# team18.net
KiCad netlist of a schematic drawn in EAGLE
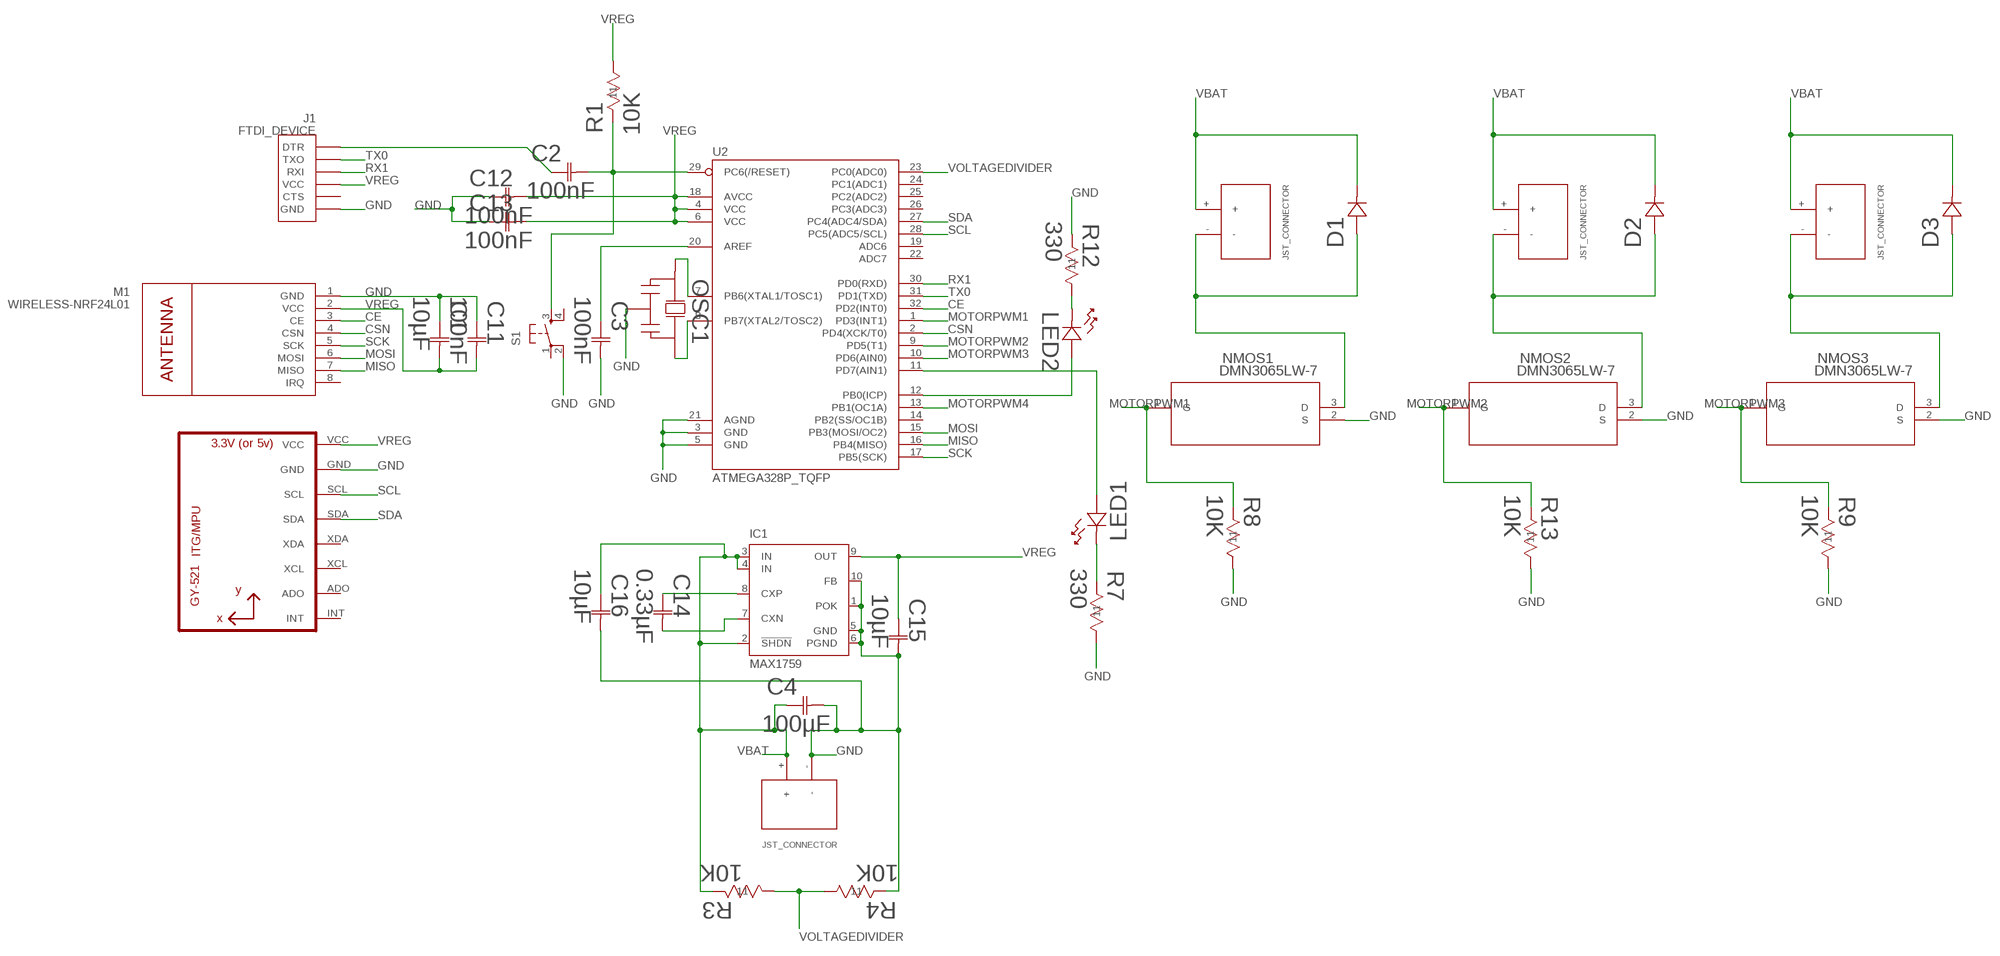
[diagram p0: schematic, sheet 1, part 1 of 2]
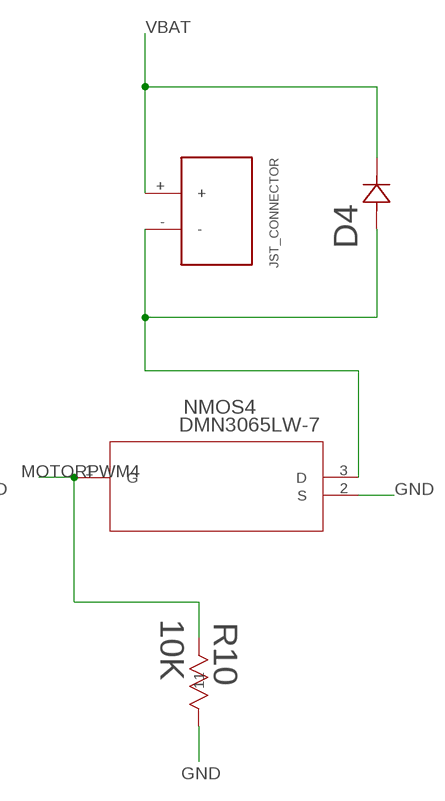
[diagram p1: schematic, sheet 1, part 2 of 2]

(export (version "E")
  (design (tool "Eeschema 10.0.6"))
  (components
    (comp (ref "BATTERY")
      (value "JST_CONNECTOR_FEMALE")
      (footprint "eagle-import:JST_CONNECTOR_FEMALE")
      (libsource (lib "eagle-import") (part "JST_CONNECTOR_FEMALE"))
    )
    (comp (ref "C1")
      (value "10µF")
      (footprint "eagle-import:G-188")
      (fields (field (name "MANUFACTURER_PART_NUMBER") "GRM188R60J106ME47D"))
      (libsource (lib "eagle-import") (part "GRM188R60J106ME47D"))
    )
    (comp (ref "C2")
      (value "100nF")
      (footprint "eagle-import:CAP_1608")
      (fields (field (name "MANUFACTURER_PART_NUMBER") "C1608X5R1H104K080AA"))
      (libsource (lib "eagle-import") (part "C1608X5R1H104K080AA"))
    )
    (comp (ref "C3")
      (value "100nF")
      (footprint "eagle-import:CAP_1608")
      (fields (field (name "MANUFACTURER_PART_NUMBER") "C1608X5R1H104K080AA"))
      (libsource (lib "eagle-import") (part "C1608X5R1H104K080AA"))
    )
    (comp (ref "C4")
      (value "100µF")
      (footprint "eagle-import:CAP_3216")
      (fields (field (name "MANUFACTURER_PART_NUMBER") "C3216X5R0J107M160AB"))
      (libsource (lib "eagle-import") (part "C3216X5R0J107M160AB"))
    )
    (comp (ref "C11")
      (value "100nF")
      (footprint "eagle-import:CAP_1608")
      (fields (field (name "MANUFACTURER_PART_NUMBER") "C1608X5R1H104K080AA"))
      (libsource (lib "eagle-import") (part "C1608X5R1H104K080AA"))
    )
    (comp (ref "C12")
      (value "100nF")
      (footprint "eagle-import:CAP_1608")
      (fields (field (name "MANUFACTURER_PART_NUMBER") "C1608X5R1H104K080AA"))
      (libsource (lib "eagle-import") (part "C1608X5R1H104K080AA"))
    )
    (comp (ref "C13")
      (value "100nF")
      (footprint "eagle-import:CAP_1608")
      (fields (field (name "MANUFACTURER_PART_NUMBER") "C1608X5R1H104K080AA"))
      (libsource (lib "eagle-import") (part "C1608X5R1H104K080AA"))
    )
    (comp (ref "C14")
      (value "0.33µF")
      (footprint "eagle-import:G-188")
      (fields (field (name "MANUFACTURER_PART_NUMBER") "GRM188R71C334KA01D"))
      (libsource (lib "eagle-import") (part "GRM188R71C334KA01D"))
    )
    (comp (ref "C15")
      (value "10µF")
      (footprint "eagle-import:G-188")
      (fields (field (name "MANUFACTURER_PART_NUMBER") "GRM188R60J106ME47D"))
      (libsource (lib "eagle-import") (part "GRM188R60J106ME47D"))
    )
    (comp (ref "C16")
      (value "10µF")
      (footprint "eagle-import:G-188")
      (fields (field (name "MANUFACTURER_PART_NUMBER") "GRM188R60J106ME47D"))
      (libsource (lib "eagle-import") (part "GRM188R60J106ME47D"))
    )
    (comp (ref "D1")
      (value "BAT60JFILM")
      (footprint "eagle-import:SOD-323")
      (libsource (lib "eagle-import") (part "BAT60JFILM"))
    )
    (comp (ref "D2")
      (value "BAT60JFILM")
      (footprint "eagle-import:SOD-323")
      (libsource (lib "eagle-import") (part "BAT60JFILM"))
    )
    (comp (ref "D3")
      (value "BAT60JFILM")
      (footprint "eagle-import:SOD-323")
      (libsource (lib "eagle-import") (part "BAT60JFILM"))
    )
    (comp (ref "D4")
      (value "BAT60JFILM")
      (footprint "eagle-import:SOD-323")
      (libsource (lib "eagle-import") (part "BAT60JFILM"))
    )
    (comp (ref "IC1")
      (value "MAX1759")
      (footprint "eagle-import:UMAX10")
      (fields (field (name "MF") "MAXIM") (field (name "MPN") "MAX1759EUB+"))
      (libsource (lib "eagle-import") (part "MAX1759"))
    )
    (comp (ref "J1")
      (value "FTDI_DEVICE")
      (footprint "eagle-import:FTDI_DEVICE_SIDE")
      (libsource (lib "eagle-import") (part "FTDI_DEVICE"))
    )
    (comp (ref "LED1")
      (value "5988070107F")
      (footprint "eagle-import:LED_DIALIGHT_598")
      (libsource (lib "eagle-import") (part "LED Red_5988070107F"))
    )
    (comp (ref "LED2")
      (value "5988070107F")
      (footprint "eagle-import:LED_DIALIGHT_598")
      (libsource (lib "eagle-import") (part "5988070107F"))
    )
    (comp (ref "M1")
      (value "WIRELESS-NRF24L01")
      (footprint "eagle-import:WIRELESS-NRF24L01")
      (libsource (lib "eagle-import") (part "WIRELESS-NRF24L01"))
    )
    (comp (ref "MOTOR1")
      (value "JST_CONNECTOR_FEMALE")
      (footprint "eagle-import:JST_CONNECTOR_FEMALE")
      (libsource (lib "eagle-import") (part "JST_CONNECTOR_FEMALE"))
    )
    (comp (ref "MOTOR2")
      (value "JST_CONNECTOR_FEMALE")
      (footprint "eagle-import:JST_CONNECTOR_FEMALE")
      (libsource (lib "eagle-import") (part "JST_CONNECTOR_FEMALE"))
    )
    (comp (ref "MOTOR3")
      (value "JST_CONNECTOR_FEMALE")
      (footprint "eagle-import:JST_CONNECTOR_FEMALE")
      (libsource (lib "eagle-import") (part "JST_CONNECTOR_FEMALE"))
    )
    (comp (ref "MOTOR4")
      (value "JST_CONNECTOR_FEMALE")
      (footprint "eagle-import:JST_CONNECTOR_FEMALE")
      (libsource (lib "eagle-import") (part "JST_CONNECTOR_FEMALE"))
    )
    (comp (ref "NMOS1")
      (value "DMN3065LW-7")
      (footprint "eagle-import:SOT-323W_NEW")
      (libsource (lib "eagle-import") (part "DMN3065LW-7"))
    )
    (comp (ref "NMOS2")
      (value "DMN3065LW-7")
      (footprint "eagle-import:SOT-323W_NEW")
      (libsource (lib "eagle-import") (part "DMN3065LW-7"))
    )
    (comp (ref "NMOS3")
      (value "DMN3065LW-7")
      (footprint "eagle-import:SOT-323W_NEW")
      (libsource (lib "eagle-import") (part "DMN3065LW-7"))
    )
    (comp (ref "NMOS4")
      (value "DMN3065LW-7")
      (footprint "eagle-import:SOT-323W_NEW")
      (libsource (lib "eagle-import") (part "DMN3065LW-7"))
    )
    (comp (ref "OSC1")
      (value "CSTCE8M00G52-R0")
      (footprint "eagle-import:CSTCE")
      (fields (field (name "MANUFACTURER_PART_NUMBER") "CSTCE8M00G52R0"))
      (libsource (lib "eagle-import") (part "CSTCE8M00G52-R0"))
    )
    (comp (ref "R1")
      (value "10K")
      (footprint "eagle-import:0603")
      (fields (field (name "MANUFACTURER_PART_NUMBER") "MCT06030C1002FP500"))
      (libsource (lib "eagle-import") (part "MCT06030C1002FP500"))
    )
    (comp (ref "R3")
      (value "10K")
      (footprint "eagle-import:0603")
      (fields (field (name "MANUFACTURER_PART_NUMBER") "MCT06030C1002FP500"))
      (libsource (lib "eagle-import") (part "MCT06030C1002FP500"))
    )
    (comp (ref "R4")
      (value "10K")
      (footprint "eagle-import:0603")
      (fields (field (name "MANUFACTURER_PART_NUMBER") "MCT06030C1002FP500"))
      (libsource (lib "eagle-import") (part "MCT06030C1002FP500"))
    )
    (comp (ref "R7")
      (value "330")
      (footprint "eagle-import:BO_CR0603")
      (fields (field (name "MANUFACTURER_PART_NUMBER") "CR0603JW331ELF"))
      (libsource (lib "eagle-import") (part "CR0603-JW-331ELF"))
    )
    (comp (ref "R8")
      (value "10K")
      (footprint "eagle-import:0603")
      (fields (field (name "MANUFACTURER_PART_NUMBER") "MCT06030C1002FP500"))
      (libsource (lib "eagle-import") (part "MCT06030C1002FP500"))
    )
    (comp (ref "R9")
      (value "10K")
      (footprint "eagle-import:0603")
      (fields (field (name "MANUFACTURER_PART_NUMBER") "MCT06030C1002FP500"))
      (libsource (lib "eagle-import") (part "MCT06030C1002FP500"))
    )
    (comp (ref "R10")
      (value "10K")
      (footprint "eagle-import:0603")
      (fields (field (name "MANUFACTURER_PART_NUMBER") "MCT06030C1002FP500"))
      (libsource (lib "eagle-import") (part "MCT06030C1002FP500"))
    )
    (comp (ref "R12")
      (value "330")
      (footprint "eagle-import:BO_CR0603")
      (fields (field (name "MANUFACTURER_PART_NUMBER") "CR0603JW331ELF"))
      (libsource (lib "eagle-import") (part "CR0603-JW-331ELF"))
    )
    (comp (ref "R13")
      (value "10K")
      (footprint "eagle-import:0603")
      (fields (field (name "MANUFACTURER_PART_NUMBER") "MCT06030C1002FP500"))
      (libsource (lib "eagle-import") (part "MCT06030C1002FP500"))
    )
    (comp (ref "S1")
      (value "TAC_SWITCHSMD")
      (footprint "eagle-import:TACTILE_SWITCH_SMD")
      (libsource (lib "eagle-import") (part "TAC_SWITCHSMD"))
    )
    (comp (ref "U1")
      (value "GY-521MPU6050")
      (footprint "eagle-import:GY-521")
      (libsource (lib "eagle-import") (part "GY-521MPU6050"))
    )
    (comp (ref "U2")
      (value "ATMEGA328P_TQFP")
      (footprint "eagle-import:TQFP32-08")
      (libsource (lib "eagle-import") (part "ATMEGA328P_TQFP"))
    )
  )
  (nets
    (net (code "1") (name "/CE") (class "Default")
      (node (ref "M1") (pin "3") (pinfunction "CE_3") (pintype "bidirectional"))
      (node (ref "U2") (pin "32") (pinfunction "PD2(INT0)_32") (pintype "bidirectional"))
    )
    (net (code "2") (name "/CSN") (class "Default")
      (node (ref "M1") (pin "4") (pinfunction "CSN_4") (pintype "bidirectional"))
      (node (ref "U2") (pin "2") (pinfunction "PD4(XCK/T0)_2") (pintype "bidirectional"))
    )
    (net (code "3") (name "/GND") (class "Default")
      (node (ref "BATTERY") (pin "-") (pinfunction "-_-") (pintype "bidirectional"))
      (node (ref "C1") (pin "1") (pinfunction "11_1") (pintype "passive"))
      (node (ref "C11") (pin "1") (pinfunction "11_1") (pintype "passive"))
      (node (ref "C12") (pin "1") (pinfunction "11_1") (pintype "passive"))
      (node (ref "C13") (pin "1") (pinfunction "11_1") (pintype "passive"))
      (node (ref "C15") (pin "2") (pinfunction "22_2") (pintype "passive"))
      (node (ref "C16") (pin "2") (pinfunction "22_2") (pintype "passive"))
      (node (ref "C3") (pin "2") (pinfunction "22_2") (pintype "passive"))
      (node (ref "C4") (pin "2") (pinfunction "22_2") (pintype "passive"))
      (node (ref "IC1") (pin "1") (pinfunction "POK_1") (pintype "open_collector"))
      (node (ref "IC1") (pin "10") (pinfunction "FB_10") (pintype "input"))
      (node (ref "IC1") (pin "5") (pinfunction "GND_5") (pintype "power_in"))
      (node (ref "IC1") (pin "6") (pinfunction "PGND_6") (pintype "power_in"))
      (node (ref "J1") (pin "P$6") (pinfunction "GND_P$6") (pintype "bidirectional"))
      (node (ref "M1") (pin "1") (pinfunction "GND_1") (pintype "power_in"))
      (node (ref "NMOS1") (pin "2") (pinfunction "S_2") (pintype "passive"))
      (node (ref "NMOS2") (pin "2") (pinfunction "S_2") (pintype "passive"))
      (node (ref "NMOS3") (pin "2") (pinfunction "S_2") (pintype "passive"))
      (node (ref "NMOS4") (pin "2") (pinfunction "S_2") (pintype "passive"))
      (node (ref "OSC1") (pin "2") (pinfunction "22_2") (pintype "passive"))
      (node (ref "R10") (pin "2") (pinfunction "22_2") (pintype "passive"))
      (node (ref "R12") (pin "1") (pinfunction "11_1") (pintype "passive"))
      (node (ref "R13") (pin "2") (pinfunction "22_2") (pintype "passive"))
      (node (ref "R4") (pin "1") (pinfunction "11_1") (pintype "passive"))
      (node (ref "R7") (pin "2") (pinfunction "22_2") (pintype "passive"))
      (node (ref "R8") (pin "2") (pinfunction "22_2") (pintype "passive"))
      (node (ref "R9") (pin "2") (pinfunction "22_2") (pintype "passive"))
      (node (ref "S1") (pin "2") (pinfunction "2_2") (pintype "passive"))
      (node (ref "U1") (pin "GND") (pinfunction "GND_GND") (pintype "bidirectional"))
      (node (ref "U2") (pin "21") (pinfunction "AGND_21") (pintype "bidirectional"))
      (node (ref "U2") (pin "3") (pinfunction "GND_3") (pintype "bidirectional"))
      (node (ref "U2") (pin "5") (pinfunction "GND_5") (pintype "bidirectional"))
    )
    (net (code "4") (name "/MISO") (class "Default")
      (node (ref "M1") (pin "7") (pinfunction "MISO_7") (pintype "bidirectional"))
      (node (ref "U2") (pin "16") (pinfunction "PB4(MISO)_16") (pintype "bidirectional"))
    )
    (net (code "5") (name "/MOSI") (class "Default")
      (node (ref "M1") (pin "6") (pinfunction "MOSI_6") (pintype "bidirectional"))
      (node (ref "U2") (pin "15") (pinfunction "PB3(MOSI/OC2)_15") (pintype "bidirectional"))
    )
    (net (code "6") (name "/MOTORPWM1") (class "Default")
      (node (ref "NMOS1") (pin "1") (pinfunction "G_1") (pintype "passive"))
      (node (ref "R8") (pin "1") (pinfunction "11_1") (pintype "passive"))
      (node (ref "U2") (pin "1") (pinfunction "PD3(INT1)_1") (pintype "bidirectional"))
    )
    (net (code "7") (name "/MOTORPWM2") (class "Default")
      (node (ref "NMOS2") (pin "1") (pinfunction "G_1") (pintype "passive"))
      (node (ref "R13") (pin "1") (pinfunction "11_1") (pintype "passive"))
      (node (ref "U2") (pin "9") (pinfunction "PD5(T1)_9") (pintype "bidirectional"))
    )
    (net (code "8") (name "/MOTORPWM3") (class "Default")
      (node (ref "NMOS3") (pin "1") (pinfunction "G_1") (pintype "passive"))
      (node (ref "R9") (pin "1") (pinfunction "11_1") (pintype "passive"))
      (node (ref "U2") (pin "10") (pinfunction "PD6(AIN0)_10") (pintype "bidirectional"))
    )
    (net (code "9") (name "/MOTORPWM4") (class "Default")
      (node (ref "NMOS4") (pin "1") (pinfunction "G_1") (pintype "passive"))
      (node (ref "R10") (pin "1") (pinfunction "11_1") (pintype "passive"))
      (node (ref "U2") (pin "13") (pinfunction "PB1(OC1A)_13") (pintype "bidirectional"))
    )
    (net (code "10") (name "/RX1") (class "Default")
      (node (ref "J1") (pin "P$3") (pinfunction "RXI_P$3") (pintype "bidirectional"))
      (node (ref "U2") (pin "30") (pinfunction "PD0(RXD)_30") (pintype "bidirectional"))
    )
    (net (code "11") (name "/SCK") (class "Default")
      (node (ref "M1") (pin "5") (pinfunction "SCK_5") (pintype "bidirectional"))
      (node (ref "U2") (pin "17") (pinfunction "PB5(SCK)_17") (pintype "bidirectional"))
    )
    (net (code "12") (name "/SCL") (class "Default")
      (node (ref "U1") (pin "SCL") (pinfunction "SCL_SCL") (pintype "bidirectional"))
      (node (ref "U2") (pin "28") (pinfunction "PC5(ADC5/SCL)_28") (pintype "bidirectional"))
    )
    (net (code "13") (name "/SDA") (class "Default")
      (node (ref "U1") (pin "SDA") (pinfunction "SDA_SDA") (pintype "bidirectional"))
      (node (ref "U2") (pin "27") (pinfunction "PC4(ADC4/SDA)_27") (pintype "bidirectional"))
    )
    (net (code "14") (name "/TX0") (class "Default")
      (node (ref "J1") (pin "P$2") (pinfunction "TXO_P$2") (pintype "bidirectional"))
      (node (ref "U2") (pin "31") (pinfunction "PD1(TXD)_31") (pintype "bidirectional"))
    )
    (net (code "15") (name "/VBAT") (class "Default")
      (node (ref "BATTERY") (pin "+") (pinfunction "+_+") (pintype "bidirectional"))
      (node (ref "C16") (pin "1") (pinfunction "11_1") (pintype "passive"))
      (node (ref "C4") (pin "1") (pinfunction "11_1") (pintype "passive"))
      (node (ref "D1") (pin "1") (pinfunction "11_1") (pintype "passive"))
      (node (ref "D2") (pin "1") (pinfunction "11_1") (pintype "passive"))
      (node (ref "D3") (pin "1") (pinfunction "11_1") (pintype "passive"))
      (node (ref "D4") (pin "1") (pinfunction "11_1") (pintype "passive"))
      (node (ref "IC1") (pin "2") (pinfunction "~{SHDN}_2") (pintype "input"))
      (node (ref "IC1") (pin "3") (pinfunction "IN_3") (pintype "input"))
      (node (ref "IC1") (pin "4") (pinfunction "IN_4") (pintype "input"))
      (node (ref "MOTOR1") (pin "+") (pinfunction "+_+") (pintype "bidirectional"))
      (node (ref "MOTOR2") (pin "+") (pinfunction "+_+") (pintype "bidirectional"))
      (node (ref "MOTOR3") (pin "+") (pinfunction "+_+") (pintype "bidirectional"))
      (node (ref "MOTOR4") (pin "+") (pinfunction "+_+") (pintype "bidirectional"))
      (node (ref "R3") (pin "1") (pinfunction "11_1") (pintype "passive"))
    )
    (net (code "16") (name "/VOLTAGEDIVIDER") (class "Default")
      (node (ref "R3") (pin "2") (pinfunction "22_2") (pintype "passive"))
      (node (ref "R4") (pin "2") (pinfunction "22_2") (pintype "passive"))
      (node (ref "U2") (pin "23") (pinfunction "PC0(ADC0)_23") (pintype "bidirectional"))
    )
    (net (code "17") (name "/VREG") (class "Default")
      (node (ref "C1") (pin "2") (pinfunction "22_2") (pintype "passive"))
      (node (ref "C11") (pin "2") (pinfunction "22_2") (pintype "passive"))
      (node (ref "C12") (pin "2") (pinfunction "22_2") (pintype "passive"))
      (node (ref "C13") (pin "2") (pinfunction "22_2") (pintype "passive"))
      (node (ref "C15") (pin "1") (pinfunction "11_1") (pintype "passive"))
      (node (ref "IC1") (pin "9") (pinfunction "OUT_9") (pintype "passive"))
      (node (ref "J1") (pin "P$4") (pinfunction "VCC_P$4") (pintype "bidirectional"))
      (node (ref "M1") (pin "2") (pinfunction "VCC_2") (pintype "power_in"))
      (node (ref "R1") (pin "2") (pinfunction "22_2") (pintype "passive"))
      (node (ref "U1") (pin "VCC") (pinfunction "VCC_VCC") (pintype "bidirectional"))
      (node (ref "U2") (pin "18") (pinfunction "AVCC_18") (pintype "bidirectional"))
      (node (ref "U2") (pin "4") (pinfunction "VCC_4") (pintype "bidirectional"))
      (node (ref "U2") (pin "6") (pinfunction "VCC_6") (pintype "bidirectional"))
    )
    (net (code "18") (name "Net-(C2-11)") (class "Default")
      (node (ref "C2") (pin "1") (pinfunction "11_1") (pintype "passive"))
      (node (ref "J1") (pin "P$1") (pinfunction "DTR_P$1") (pintype "bidirectional"))
    )
    (net (code "19") (name "Net-(C2-22)") (class "Default")
      (node (ref "C2") (pin "2") (pinfunction "22_2") (pintype "passive"))
      (node (ref "R1") (pin "1") (pinfunction "11_1") (pintype "passive"))
      (node (ref "S1") (pin "3") (pinfunction "3_3") (pintype "passive"))
      (node (ref "U2") (pin "29") (pinfunction "PC6(/RESET)_29") (pintype "bidirectional"))
    )
    (net (code "20") (name "Net-(C3-11)") (class "Default")
      (node (ref "C3") (pin "1") (pinfunction "11_1") (pintype "passive"))
      (node (ref "U2") (pin "20") (pinfunction "AREF_20") (pintype "bidirectional"))
    )
    (net (code "21") (name "Net-(C14-11)") (class "Default")
      (node (ref "C14") (pin "1") (pinfunction "11_1") (pintype "passive"))
      (node (ref "IC1") (pin "8") (pinfunction "CXP_8") (pintype "input"))
    )
    (net (code "22") (name "Net-(C14-22)") (class "Default")
      (node (ref "C14") (pin "2") (pinfunction "22_2") (pintype "passive"))
      (node (ref "IC1") (pin "7") (pinfunction "CXN_7") (pintype "input"))
    )
    (net (code "23") (name "Net-(D1-22)") (class "Default")
      (node (ref "D1") (pin "2") (pinfunction "22_2") (pintype "passive"))
      (node (ref "MOTOR1") (pin "-") (pinfunction "-_-") (pintype "bidirectional"))
      (node (ref "NMOS1") (pin "3") (pinfunction "D_3") (pintype "passive"))
    )
    (net (code "24") (name "Net-(D2-22)") (class "Default")
      (node (ref "D2") (pin "2") (pinfunction "22_2") (pintype "passive"))
      (node (ref "MOTOR2") (pin "-") (pinfunction "-_-") (pintype "bidirectional"))
      (node (ref "NMOS2") (pin "3") (pinfunction "D_3") (pintype "passive"))
    )
    (net (code "25") (name "Net-(D3-22)") (class "Default")
      (node (ref "D3") (pin "2") (pinfunction "22_2") (pintype "passive"))
      (node (ref "MOTOR3") (pin "-") (pinfunction "-_-") (pintype "bidirectional"))
      (node (ref "NMOS3") (pin "3") (pinfunction "D_3") (pintype "passive"))
    )
    (net (code "26") (name "Net-(D4-22)") (class "Default")
      (node (ref "D4") (pin "2") (pinfunction "22_2") (pintype "passive"))
      (node (ref "MOTOR4") (pin "-") (pinfunction "-_-") (pintype "bidirectional"))
      (node (ref "NMOS4") (pin "3") (pinfunction "D_3") (pintype "passive"))
    )
    (net (code "27") (name "Net-(LED1-11)") (class "Default")
      (node (ref "LED1") (pin "1") (pinfunction "11_1") (pintype "passive"))
      (node (ref "R7") (pin "1") (pinfunction "11_1") (pintype "passive"))
    )
    (net (code "28") (name "Net-(LED1-22)") (class "Default")
      (node (ref "LED1") (pin "2") (pinfunction "22_2") (pintype "passive"))
      (node (ref "U2") (pin "11") (pinfunction "PD7(AIN1)_11") (pintype "bidirectional"))
    )
    (net (code "29") (name "Net-(LED2-11)") (class "Default")
      (node (ref "LED2") (pin "1") (pinfunction "11_1") (pintype "passive"))
      (node (ref "R12") (pin "2") (pinfunction "22_2") (pintype "passive"))
    )
    (net (code "30") (name "Net-(LED2-22)") (class "Default")
      (node (ref "LED2") (pin "2") (pinfunction "22_2") (pintype "passive"))
      (node (ref "U2") (pin "12") (pinfunction "PB0(ICP)_12") (pintype "bidirectional"))
    )
    (net (code "31") (name "Net-(OSC1-11)") (class "Default")
      (node (ref "OSC1") (pin "1") (pinfunction "11_1") (pintype "passive"))
      (node (ref "U2") (pin "8") (pinfunction "PB7(XTAL2/TOSC2)_8") (pintype "bidirectional"))
    )
    (net (code "32") (name "Net-(OSC1-33)") (class "Default")
      (node (ref "OSC1") (pin "3") (pinfunction "33_3") (pintype "passive"))
      (node (ref "U2") (pin "7") (pinfunction "PB6(XTAL1/TOSC1)_7") (pintype "bidirectional"))
    )
    (net (code "33") (name "unconnected-(J1-CTS-PadP$5)") (class "Default")
      (node (ref "J1") (pin "P$5") (pinfunction "CTS_P$5") (pintype "bidirectional"))
    )
    (net (code "34") (name "unconnected-(M1-IRQ-Pad8)") (class "Default")
      (node (ref "M1") (pin "8") (pinfunction "IRQ_8") (pintype "bidirectional"))
    )
    (net (code "35") (name "unconnected-(S1-Pad1)") (class "Default")
      (node (ref "S1") (pin "1") (pinfunction "1_1") (pintype "passive"))
    )
    (net (code "36") (name "unconnected-(S1-Pad4)") (class "Default")
      (node (ref "S1") (pin "4") (pinfunction "4_4") (pintype "passive"))
    )
    (net (code "37") (name "unconnected-(U1-PadADO)") (class "Default")
      (node (ref "U1") (pin "ADO") (pinfunction "ADO_ADO") (pintype "bidirectional"))
    )
    (net (code "38") (name "unconnected-(U1-PadINT)") (class "Default")
      (node (ref "U1") (pin "INT") (pinfunction "INT_INT") (pintype "bidirectional"))
    )
    (net (code "39") (name "unconnected-(U1-PadXCL)") (class "Default")
      (node (ref "U1") (pin "XCL") (pinfunction "XCL_XCL") (pintype "bidirectional"))
    )
    (net (code "40") (name "unconnected-(U1-PadXDA)") (class "Default")
      (node (ref "U1") (pin "XDA") (pinfunction "XDA_XDA") (pintype "bidirectional"))
    )
    (net (code "41") (name "unconnected-(U2-ADC6-Pad19)") (class "Default")
      (node (ref "U2") (pin "19") (pinfunction "ADC6_19") (pintype "bidirectional"))
    )
    (net (code "42") (name "unconnected-(U2-ADC7-Pad22)") (class "Default")
      (node (ref "U2") (pin "22") (pinfunction "ADC7_22") (pintype "bidirectional"))
    )
    (net (code "43") (name "unconnected-(U2-PB2(SS{slash}OC1B)-Pad14)") (class "Default")
      (node (ref "U2") (pin "14") (pinfunction "PB2(SS/OC1B)_14") (pintype "bidirectional"))
    )
    (net (code "44") (name "unconnected-(U2-PC1(ADC1)-Pad24)") (class "Default")
      (node (ref "U2") (pin "24") (pinfunction "PC1(ADC1)_24") (pintype "bidirectional"))
    )
    (net (code "45") (name "unconnected-(U2-PC2(ADC2)-Pad25)") (class "Default")
      (node (ref "U2") (pin "25") (pinfunction "PC2(ADC2)_25") (pintype "bidirectional"))
    )
    (net (code "46") (name "unconnected-(U2-PC3(ADC3)-Pad26)") (class "Default")
      (node (ref "U2") (pin "26") (pinfunction "PC3(ADC3)_26") (pintype "bidirectional"))
    )
  )
)
